# USRP.net
KiCad netlist of a schematic drawn in Altium Designer
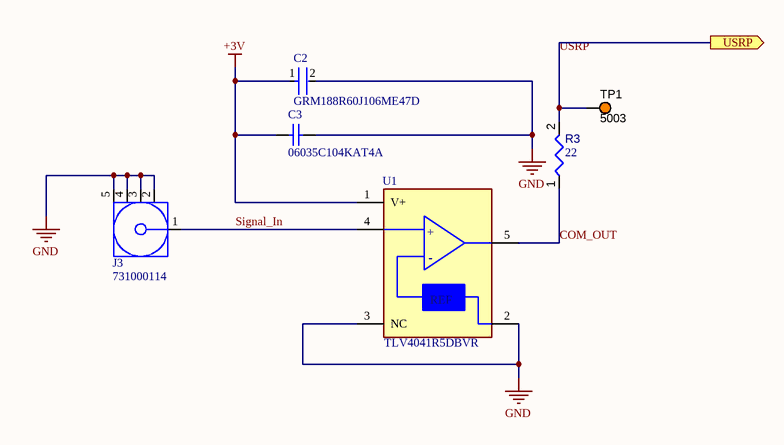
[diagram p0: USRP.SchDoc]

(export (version "E")
  (design (tool "Eeschema 10.0.6"))
  (components
    (comp (ref "C2")
      (value "GRM188R60J106ME47D")
      (footprint "FP-GRM188-0_1-e0_2_0_55-IPC_A")
      (description "Chip Multilayer Ceramic Capacitors for General Purpose, 0603, 10uF, X5R, 15%, 20%, 6.3V")
      (fields (field (name "VOLTAGE") "6.3V") (field (name "TOLERANCE") "20%"))
      (libsource (lib "Altium Content Vault") (part "02cd4be3c70576c341d710602a673aa"))
    )
    (comp (ref "C3")
      (value "06035C104KAT4A")
      (footprint "CAPC1608X90X35LL15T15")
      (fields (field (name "MANUFACTURER") "AVX Interconnect / Elco"))
      (libsource (lib "Altium Content Vault") (part "CAP"))
    )
    (comp (ref "J3")
      (value "731000114")
      (footprint "MOLX-731000114_V")
      (description "SMA Right-Angle PCB Jack Receptacle, Brass Body, Gold Plated, 50 Ohm, 5-Pin THD, RoHS, Tray")
      (fields (field (name "MANUFACTURER") "Molex"))
      (libsource (lib "Altium Content Vault") (part "CN-S-4F-RF5"))
    )
    (comp (ref "R3")
      (value "22")
      (footprint "RESC1609X50X30ML08T20")
      (description "Chip Resistor, 22 Ohm, +/- 1%, 100 mW, -55 to 155 degC, 0603 (1608 Metric)")
      (fields (field (name "POWER") "100mW") (field (name "TOLERANCE") "1%"))
      (libsource (lib "Nick") (part "RES-2"))
    )
    (comp (ref "TP1")
      (value "5003")
      (footprint "KSTN-5003")
      (description "Test Point, Orange, Height 4.6 mm, Tail Length 3 mm, 1-Pin THD, RoHS")
      (fields (field (name "MANUFACTURER") "Keystone"))
      (libsource (lib "Nick") (part "TESTPOINT_ORANGE"))
    )
    (comp (ref "U1")
      (value "TLV4041R5DBVR")
      (footprint "FP-DBV0005A-IPC_C")
      (description "LOW-POWER COMPARATOR WITH REFERE")
      (libsource (lib "Altium Content Vault") (part "9caaae710b6845d4724b5c5097c5400"))
    )
  )
  (nets
    (net (code "1") (name "+3V") (class "Default")
      (node (ref "C2") (pin "1") (pinfunction "1_1") (pintype "passive"))
      (node (ref "C3") (pin "2") (pinfunction "2_2") (pintype "passive"))
      (node (ref "U1") (pin "1") (pinfunction "V+_1") (pintype "power_in"))
    )
    (net (code "2") (name "/COM_OUT") (class "Default")
      (node (ref "R3") (pin "1") (pinfunction "1_1") (pintype "passive"))
      (node (ref "U1") (pin "5") (pinfunction "OUT_5") (pintype "passive"))
    )
    (net (code "3") (name "/Signal_In") (class "Default")
      (node (ref "J3") (pin "1") (pinfunction "1_1") (pintype "passive"))
      (node (ref "U1") (pin "4") (pinfunction "IN_4") (pintype "tri_state"))
    )
    (net (code "4") (name "/USRP") (class "Default")
      (node (ref "R3") (pin "2") (pinfunction "2_2") (pintype "passive"))
      (node (ref "TP1") (pin "1") (pinfunction "1_1") (pintype "passive"))
    )
    (net (code "5") (name "GND") (class "Default")
      (node (ref "C2") (pin "2") (pinfunction "2_2") (pintype "passive"))
      (node (ref "C3") (pin "1") (pinfunction "1_1") (pintype "passive"))
      (node (ref "J3") (pin "2") (pinfunction "2_2") (pintype "passive"))
      (node (ref "J3") (pin "3") (pinfunction "3_3") (pintype "passive"))
      (node (ref "J3") (pin "4") (pinfunction "4_4") (pintype "passive"))
      (node (ref "J3") (pin "5") (pinfunction "5_5") (pintype "passive"))
      (node (ref "U1") (pin "2") (pinfunction "V-_2") (pintype "power_in"))
      (node (ref "U1") (pin "3") (pinfunction "NC_3") (pintype "passive"))
    )
  )
)
